# PL_Ethernet.net
KiCad netlist of a schematic drawn in Altium Designer
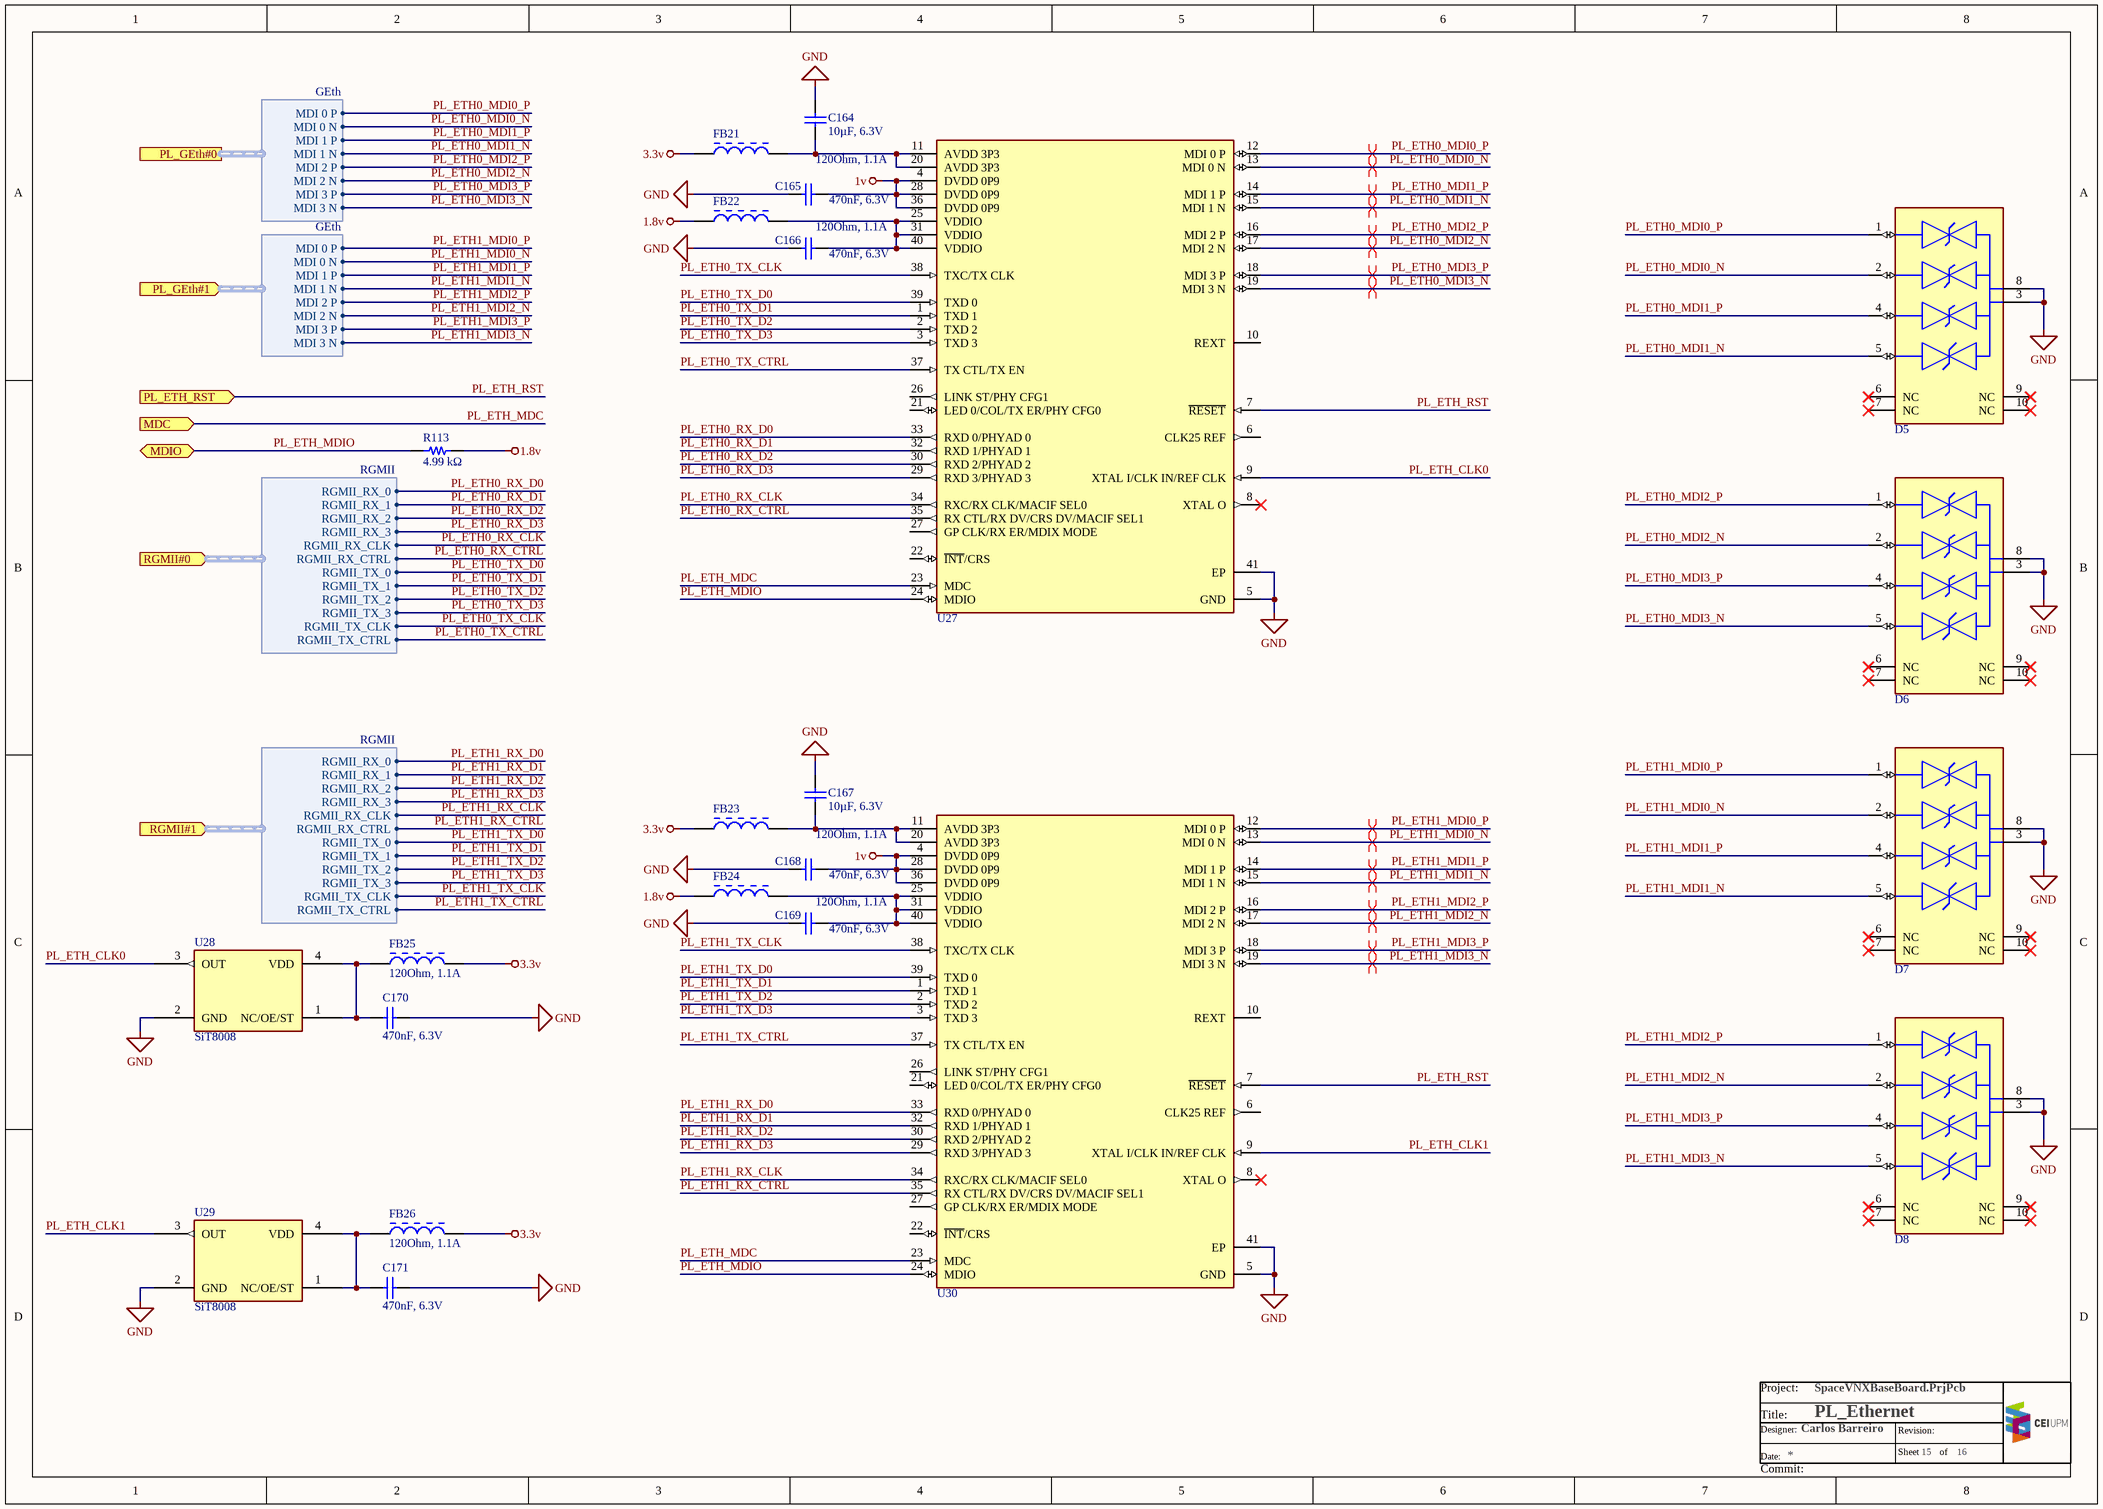
[diagram p0: PL_Ethernet.SchDoc]

(export (version "E")
  (design (tool "Eeschema 10.0.6"))
  (components
    (comp (ref "C164")
      (value "10µF, 6.3V")
      (footprint "WURTH_WCAP-CSGP_0402")
      (description "WCAP-CSGP Multilayer Ceramic Chip Capacitor, General Purpose, size 0402, X5R, 10uF, 6.3V")
      (fields
        (field (name "MANUFACTURER PART NUMBER") "885012105020")
        (field (name "MANUFACTURER") "Wurth Elektronik")
      )
      (libsource (lib "SpaceVNX") (part "885012105020"))
    )
    (comp (ref "C165")
      (value "470nF, 6.3V")
      (footprint "WURTH_WCAP-CSGP_0402")
      (description "WCAP-CSGP Multilayer Ceramic Chip Capacitor, General Purpose, size 0402, X5R, 470nF, 6.3V")
      (fields
        (field (name "MANUFACTURER PART NUMBER") "885012105004")
        (field (name "MANUFACTURER") "Wurth Elektronik")
      )
      (libsource (lib "SpaceVNX") (part "885012105004"))
    )
    (comp (ref "C166")
      (value "470nF, 6.3V")
      (footprint "WURTH_WCAP-CSGP_0402")
      (description "WCAP-CSGP Multilayer Ceramic Chip Capacitor, General Purpose, size 0402, X5R, 470nF, 6.3V")
      (fields
        (field (name "MANUFACTURER PART NUMBER") "885012105004")
        (field (name "MANUFACTURER") "Wurth Elektronik")
      )
      (libsource (lib "SpaceVNX") (part "885012105004"))
    )
    (comp (ref "C167")
      (value "10µF, 6.3V")
      (footprint "WURTH_WCAP-CSGP_0402")
      (description "WCAP-CSGP Multilayer Ceramic Chip Capacitor, General Purpose, size 0402, X5R, 10uF, 6.3V")
      (fields
        (field (name "MANUFACTURER PART NUMBER") "885012105020")
        (field (name "MANUFACTURER") "Wurth Elektronik")
      )
      (libsource (lib "SpaceVNX") (part "885012105020"))
    )
    (comp (ref "C168")
      (value "470nF, 6.3V")
      (footprint "WURTH_WCAP-CSGP_0402")
      (description "WCAP-CSGP Multilayer Ceramic Chip Capacitor, General Purpose, size 0402, X5R, 470nF, 6.3V")
      (fields
        (field (name "MANUFACTURER PART NUMBER") "885012105004")
        (field (name "MANUFACTURER") "Wurth Elektronik")
      )
      (libsource (lib "SpaceVNX") (part "885012105004"))
    )
    (comp (ref "C169")
      (value "470nF, 6.3V")
      (footprint "WURTH_WCAP-CSGP_0402")
      (description "WCAP-CSGP Multilayer Ceramic Chip Capacitor, General Purpose, size 0402, X5R, 470nF, 6.3V")
      (fields
        (field (name "MANUFACTURER PART NUMBER") "885012105004")
        (field (name "MANUFACTURER") "Wurth Elektronik")
      )
      (libsource (lib "SpaceVNX") (part "885012105004"))
    )
    (comp (ref "C170")
      (value "470nF, 6.3V")
      (footprint "WURTH_WCAP-CSGP_0402")
      (description "WCAP-CSGP Multilayer Ceramic Chip Capacitor, General Purpose, size 0402, X5R, 470nF, 6.3V")
      (fields
        (field (name "MANUFACTURER PART NUMBER") "885012105004")
        (field (name "MANUFACTURER") "Wurth Elektronik")
      )
      (libsource (lib "SpaceVNX") (part "885012105004"))
    )
    (comp (ref "C171")
      (value "470nF, 6.3V")
      (footprint "WURTH_WCAP-CSGP_0402")
      (description "WCAP-CSGP Multilayer Ceramic Chip Capacitor, General Purpose, size 0402, X5R, 470nF, 6.3V")
      (fields
        (field (name "MANUFACTURER PART NUMBER") "885012105004")
        (field (name "MANUFACTURER") "Wurth Elektronik")
      )
      (libsource (lib "SpaceVNX") (part "885012105004"))
    )
    (comp (ref "D5")
      (value "ESD204DQAR")
      (footprint "TEXAS_USON10")
      (description "ESD204 4-Channel Low-Capacitance Surge and ESD Protection Diode")
      (libsource (lib "SpaceVNX") (part "ESD204DQAR"))
    )
    (comp (ref "D6")
      (value "ESD204DQAR")
      (footprint "TEXAS_USON10")
      (description "ESD204 4-Channel Low-Capacitance Surge and ESD Protection Diode")
      (libsource (lib "SpaceVNX") (part "ESD204DQAR"))
    )
    (comp (ref "D7")
      (value "ESD204DQAR")
      (footprint "TEXAS_USON10")
      (description "ESD204 4-Channel Low-Capacitance Surge and ESD Protection Diode")
      (libsource (lib "SpaceVNX") (part "ESD204DQAR"))
    )
    (comp (ref "D8")
      (value "ESD204DQAR")
      (footprint "TEXAS_USON10")
      (description "ESD204 4-Channel Low-Capacitance Surge and ESD Protection Diode")
      (libsource (lib "SpaceVNX") (part "ESD204DQAR"))
    )
    (comp (ref "FB21")
      (value "120Ohm, 1.1A")
      (footprint "WURTH-CBF_0402")
      (description "WE-CBF SMT EMI Suppression Ferrite Bead, size 0402, 120Ohm, 1.1A")
      (fields
        (field (name "MANUFACTURER PART NUMBER") "74279271")
        (field (name "MANUFACTURER") "Wurth Elektronik")
      )
      (libsource (lib "SpaceVNX") (part "74279271"))
    )
    (comp (ref "FB22")
      (value "120Ohm, 1.1A")
      (footprint "WURTH-CBF_0402")
      (description "WE-CBF SMT EMI Suppression Ferrite Bead, size 0402, 120Ohm, 1.1A")
      (fields
        (field (name "MANUFACTURER PART NUMBER") "74279271")
        (field (name "MANUFACTURER") "Wurth Elektronik")
      )
      (libsource (lib "SpaceVNX") (part "74279271"))
    )
    (comp (ref "FB23")
      (value "120Ohm, 1.1A")
      (footprint "WURTH-CBF_0402")
      (description "WE-CBF SMT EMI Suppression Ferrite Bead, size 0402, 120Ohm, 1.1A")
      (fields
        (field (name "MANUFACTURER PART NUMBER") "74279271")
        (field (name "MANUFACTURER") "Wurth Elektronik")
      )
      (libsource (lib "SpaceVNX") (part "74279271"))
    )
    (comp (ref "FB24")
      (value "120Ohm, 1.1A")
      (footprint "WURTH-CBF_0402")
      (description "WE-CBF SMT EMI Suppression Ferrite Bead, size 0402, 120Ohm, 1.1A")
      (fields
        (field (name "MANUFACTURER PART NUMBER") "74279271")
        (field (name "MANUFACTURER") "Wurth Elektronik")
      )
      (libsource (lib "SpaceVNX") (part "74279271"))
    )
    (comp (ref "FB25")
      (value "120Ohm, 1.1A")
      (footprint "WURTH-CBF_0402")
      (description "WE-CBF SMT EMI Suppression Ferrite Bead, size 0402, 120Ohm, 1.1A")
      (fields
        (field (name "MANUFACTURER PART NUMBER") "74279271")
        (field (name "MANUFACTURER") "Wurth Elektronik")
      )
      (libsource (lib "SpaceVNX") (part "74279271"))
    )
    (comp (ref "FB26")
      (value "120Ohm, 1.1A")
      (footprint "WURTH-CBF_0402")
      (description "WE-CBF SMT EMI Suppression Ferrite Bead, size 0402, 120Ohm, 1.1A")
      (fields
        (field (name "MANUFACTURER PART NUMBER") "74279271")
        (field (name "MANUFACTURER") "Wurth Elektronik")
      )
      (libsource (lib "SpaceVNX") (part "74279271"))
    )
    (comp (ref "R113")
      (value "4.99 kΩ")
      (footprint "PANASONIC_ERJ2G_0402")
      (description "General Purpose Thick Film Chip Resistors")
      (fields (field (name "MANUFACTURER") "Panasonic"))
      (libsource (lib "SpaceVNX") (part "ERJ2RKF4991X"))
    )
    (comp (ref "U27")
      (value "ADIN1300CCPZ")
      (footprint "ADI_LFCSP40")
      (description "Robust, Industrial, Low Latency and Low Power 10 Mbps, 100 Mbps, and 1 Gbps Ethernet PHY")
      (libsource (lib "SpaceVNX") (part "ADIN1300CCPZ"))
    )
    (comp (ref "U28")
      (value "SiT8008")
      (footprint "SiTime_5032_4")
      (libsource (lib "SpaceVNX") (part "SiT8008"))
    )
    (comp (ref "U29")
      (value "SiT8008")
      (footprint "SiTime_5032_4")
      (libsource (lib "SpaceVNX") (part "SiT8008"))
    )
    (comp (ref "U30")
      (value "ADIN1300CCPZ")
      (footprint "ADI_LFCSP40")
      (description "Robust, Industrial, Low Latency and Low Power 10 Mbps, 100 Mbps, and 1 Gbps Ethernet PHY")
      (libsource (lib "SpaceVNX") (part "ADIN1300CCPZ"))
    )
  )
  (nets
    (net (code "3") (name "/PL_ETH0_MDI0_N") (class "Default")
      (node (ref "D5") (pin "2") (pinfunction "IO2_2") (pintype "bidirectional"))
      (node (ref "U27") (pin "13") (pinfunction "MDI_0_N_13") (pintype "bidirectional"))
    )
    (net (code "4") (name "/PL_ETH0_MDI0_P") (class "Default")
      (node (ref "D5") (pin "1") (pinfunction "IO1_1") (pintype "bidirectional"))
      (node (ref "U27") (pin "12") (pinfunction "MDI_0_P_12") (pintype "bidirectional"))
    )
    (net (code "5") (name "/PL_ETH0_MDI1_N") (class "Default")
      (node (ref "D5") (pin "5") (pinfunction "IO4_5") (pintype "bidirectional"))
      (node (ref "U27") (pin "15") (pinfunction "MDI_1_N_15") (pintype "bidirectional"))
    )
    (net (code "6") (name "/PL_ETH0_MDI1_P") (class "Default")
      (node (ref "D5") (pin "4") (pinfunction "IO3_4") (pintype "bidirectional"))
      (node (ref "U27") (pin "14") (pinfunction "MDI_1_P_14") (pintype "bidirectional"))
    )
    (net (code "7") (name "/PL_ETH0_MDI2_N") (class "Default")
      (node (ref "D6") (pin "2") (pinfunction "IO2_2") (pintype "bidirectional"))
      (node (ref "U27") (pin "17") (pinfunction "MDI_2_N_17") (pintype "bidirectional"))
    )
    (net (code "8") (name "/PL_ETH0_MDI2_P") (class "Default")
      (node (ref "D6") (pin "1") (pinfunction "IO1_1") (pintype "bidirectional"))
      (node (ref "U27") (pin "16") (pinfunction "MDI_2_P_16") (pintype "bidirectional"))
    )
    (net (code "9") (name "/PL_ETH0_MDI3_N") (class "Default")
      (node (ref "D6") (pin "5") (pinfunction "IO4_5") (pintype "bidirectional"))
      (node (ref "U27") (pin "19") (pinfunction "MDI_3_N_19") (pintype "bidirectional"))
    )
    (net (code "10") (name "/PL_ETH0_MDI3_P") (class "Default")
      (node (ref "D6") (pin "4") (pinfunction "IO3_4") (pintype "bidirectional"))
      (node (ref "U27") (pin "18") (pinfunction "MDI_3_P_18") (pintype "bidirectional"))
    )
    (net (code "11") (name "/PL_ETH0_RX_CLK") (class "Default")
      (node (ref "U27") (pin "34") (pinfunction "RXC/RX_CLK/MACIF_SEL0_34") (pintype "output"))
    )
    (net (code "12") (name "/PL_ETH0_RX_CTRL") (class "Default")
      (node (ref "U27") (pin "35") (pinfunction "RX_CTL/RX_DV/CRS_DV/MACIF_SEL1_35") (pintype "output"))
    )
    (net (code "13") (name "/PL_ETH0_RX_D0") (class "Default")
      (node (ref "U27") (pin "33") (pinfunction "RXD_0/PHYAD_0_33") (pintype "output"))
    )
    (net (code "14") (name "/PL_ETH0_RX_D1") (class "Default")
      (node (ref "U27") (pin "32") (pinfunction "RXD_1/PHYAD_1_32") (pintype "output"))
    )
    (net (code "15") (name "/PL_ETH0_RX_D2") (class "Default")
      (node (ref "U27") (pin "30") (pinfunction "RXD_2/PHYAD_2_30") (pintype "output"))
    )
    (net (code "16") (name "/PL_ETH0_RX_D3") (class "Default")
      (node (ref "U27") (pin "29") (pinfunction "RXD_3/PHYAD_3_29") (pintype "output"))
    )
    (net (code "17") (name "/PL_ETH0_TX_CLK") (class "Default")
      (node (ref "U27") (pin "38") (pinfunction "TXC/TX_CLK_38") (pintype "input"))
    )
    (net (code "18") (name "/PL_ETH0_TX_CTRL") (class "Default")
      (node (ref "U27") (pin "37") (pinfunction "TX_CTL/TX_EN_37") (pintype "input"))
    )
    (net (code "19") (name "/PL_ETH0_TX_D0") (class "Default")
      (node (ref "U27") (pin "39") (pinfunction "TXD_0_39") (pintype "input"))
    )
    (net (code "20") (name "/PL_ETH0_TX_D1") (class "Default")
      (node (ref "U27") (pin "1") (pinfunction "TXD_1_1") (pintype "input"))
    )
    (net (code "21") (name "/PL_ETH0_TX_D2") (class "Default")
      (node (ref "U27") (pin "2") (pinfunction "TXD_2_2") (pintype "input"))
    )
    (net (code "22") (name "/PL_ETH0_TX_D3") (class "Default")
      (node (ref "U27") (pin "3") (pinfunction "TXD_3_3") (pintype "input"))
    )
    (net (code "23") (name "/PL_ETH1_MDI0_N") (class "Default")
      (node (ref "D7") (pin "2") (pinfunction "IO2_2") (pintype "bidirectional"))
      (node (ref "U30") (pin "13") (pinfunction "MDI_0_N_13") (pintype "bidirectional"))
    )
    (net (code "24") (name "/PL_ETH1_MDI0_P") (class "Default")
      (node (ref "D7") (pin "1") (pinfunction "IO1_1") (pintype "bidirectional"))
      (node (ref "U30") (pin "12") (pinfunction "MDI_0_P_12") (pintype "bidirectional"))
    )
    (net (code "25") (name "/PL_ETH1_MDI1_N") (class "Default")
      (node (ref "D7") (pin "5") (pinfunction "IO4_5") (pintype "bidirectional"))
      (node (ref "U30") (pin "15") (pinfunction "MDI_1_N_15") (pintype "bidirectional"))
    )
    (net (code "26") (name "/PL_ETH1_MDI1_P") (class "Default")
      (node (ref "D7") (pin "4") (pinfunction "IO3_4") (pintype "bidirectional"))
      (node (ref "U30") (pin "14") (pinfunction "MDI_1_P_14") (pintype "bidirectional"))
    )
    (net (code "27") (name "/PL_ETH1_MDI2_N") (class "Default")
      (node (ref "D8") (pin "2") (pinfunction "IO2_2") (pintype "bidirectional"))
      (node (ref "U30") (pin "17") (pinfunction "MDI_2_N_17") (pintype "bidirectional"))
    )
    (net (code "28") (name "/PL_ETH1_MDI2_P") (class "Default")
      (node (ref "D8") (pin "1") (pinfunction "IO1_1") (pintype "bidirectional"))
      (node (ref "U30") (pin "16") (pinfunction "MDI_2_P_16") (pintype "bidirectional"))
    )
    (net (code "29") (name "/PL_ETH1_MDI3_N") (class "Default")
      (node (ref "D8") (pin "5") (pinfunction "IO4_5") (pintype "bidirectional"))
      (node (ref "U30") (pin "19") (pinfunction "MDI_3_N_19") (pintype "bidirectional"))
    )
    (net (code "30") (name "/PL_ETH1_MDI3_P") (class "Default")
      (node (ref "D8") (pin "4") (pinfunction "IO3_4") (pintype "bidirectional"))
      (node (ref "U30") (pin "18") (pinfunction "MDI_3_P_18") (pintype "bidirectional"))
    )
    (net (code "31") (name "/PL_ETH1_RX_CLK") (class "Default")
      (node (ref "U30") (pin "34") (pinfunction "RXC/RX_CLK/MACIF_SEL0_34") (pintype "output"))
    )
    (net (code "32") (name "/PL_ETH1_RX_CTRL") (class "Default")
      (node (ref "U30") (pin "35") (pinfunction "RX_CTL/RX_DV/CRS_DV/MACIF_SEL1_35") (pintype "output"))
    )
    (net (code "33") (name "/PL_ETH1_RX_D0") (class "Default")
      (node (ref "U30") (pin "33") (pinfunction "RXD_0/PHYAD_0_33") (pintype "output"))
    )
    (net (code "34") (name "/PL_ETH1_RX_D1") (class "Default")
      (node (ref "U30") (pin "32") (pinfunction "RXD_1/PHYAD_1_32") (pintype "output"))
    )
    (net (code "35") (name "/PL_ETH1_RX_D2") (class "Default")
      (node (ref "U30") (pin "30") (pinfunction "RXD_2/PHYAD_2_30") (pintype "output"))
    )
    (net (code "36") (name "/PL_ETH1_RX_D3") (class "Default")
      (node (ref "U30") (pin "29") (pinfunction "RXD_3/PHYAD_3_29") (pintype "output"))
    )
    (net (code "37") (name "/PL_ETH1_TX_CLK") (class "Default")
      (node (ref "U30") (pin "38") (pinfunction "TXC/TX_CLK_38") (pintype "input"))
    )
    (net (code "38") (name "/PL_ETH1_TX_CTRL") (class "Default")
      (node (ref "U30") (pin "37") (pinfunction "TX_CTL/TX_EN_37") (pintype "input"))
    )
    (net (code "39") (name "/PL_ETH1_TX_D0") (class "Default")
      (node (ref "U30") (pin "39") (pinfunction "TXD_0_39") (pintype "input"))
    )
    (net (code "40") (name "/PL_ETH1_TX_D1") (class "Default")
      (node (ref "U30") (pin "1") (pinfunction "TXD_1_1") (pintype "input"))
    )
    (net (code "41") (name "/PL_ETH1_TX_D2") (class "Default")
      (node (ref "U30") (pin "2") (pinfunction "TXD_2_2") (pintype "input"))
    )
    (net (code "42") (name "/PL_ETH1_TX_D3") (class "Default")
      (node (ref "U30") (pin "3") (pinfunction "TXD_3_3") (pintype "input"))
    )
    (net (code "43") (name "/PL_ETH_CLK0") (class "Default")
      (node (ref "U27") (pin "9") (pinfunction "XTAL_I/CLK_IN/REF_CLK_9") (pintype "input"))
      (node (ref "U28") (pin "3") (pinfunction "OUT_3") (pintype "output"))
    )
    (net (code "44") (name "/PL_ETH_CLK1") (class "Default")
      (node (ref "U29") (pin "3") (pinfunction "OUT_3") (pintype "output"))
      (node (ref "U30") (pin "9") (pinfunction "XTAL_I/CLK_IN/REF_CLK_9") (pintype "input"))
    )
    (net (code "45") (name "/PL_ETH_MDC") (class "Default")
      (node (ref "U27") (pin "23") (pinfunction "MDC_23") (pintype "input"))
      (node (ref "U30") (pin "23") (pinfunction "MDC_23") (pintype "input"))
    )
    (net (code "46") (name "/PL_ETH_MDIO") (class "Default")
      (node (ref "R113") (pin "1") (pinfunction "1_1") (pintype "passive"))
      (node (ref "U27") (pin "24") (pinfunction "MDIO_24") (pintype "bidirectional"))
      (node (ref "U30") (pin "24") (pinfunction "MDIO_24") (pintype "bidirectional"))
    )
    (net (code "47") (name "/PL_ETH_RST") (class "Default")
      (node (ref "U27") (pin "7") (pinfunction "~{RESET}_7") (pintype "input"))
      (node (ref "U30") (pin "7") (pinfunction "~{RESET}_7") (pintype "input"))
    )
    (net (code "50") (name "1.8v") (class "Default")
      (node (ref "FB22") (pin "1") (pinfunction "1_1") (pintype "passive"))
      (node (ref "FB24") (pin "1") (pinfunction "1_1") (pintype "passive"))
      (node (ref "R113") (pin "2") (pinfunction "2_2") (pintype "passive"))
    )
    (net (code "51") (name "1v") (class "Default")
      (node (ref "C165") (pin "2") (pinfunction "2_2") (pintype "passive"))
      (node (ref "C168") (pin "2") (pinfunction "2_2") (pintype "passive"))
      (node (ref "U27") (pin "28") (pinfunction "DVDD_0P9_28") (pintype "power_in"))
      (node (ref "U27") (pin "36") (pinfunction "DVDD_0P9_36") (pintype "power_in"))
      (node (ref "U27") (pin "4") (pinfunction "DVDD_0P9_4") (pintype "power_in"))
      (node (ref "U30") (pin "28") (pinfunction "DVDD_0P9_28") (pintype "power_in"))
      (node (ref "U30") (pin "36") (pinfunction "DVDD_0P9_36") (pintype "power_in"))
      (node (ref "U30") (pin "4") (pinfunction "DVDD_0P9_4") (pintype "power_in"))
    )
    (net (code "52") (name "3.3v") (class "Default")
      (node (ref "FB21") (pin "1") (pinfunction "1_1") (pintype "passive"))
      (node (ref "FB23") (pin "1") (pinfunction "1_1") (pintype "passive"))
      (node (ref "FB25") (pin "2") (pinfunction "2_2") (pintype "passive"))
      (node (ref "FB26") (pin "2") (pinfunction "2_2") (pintype "passive"))
    )
    (net (code "53") (name "GND") (class "Default")
      (node (ref "C164") (pin "2") (pinfunction "2_2") (pintype "passive"))
      (node (ref "C165") (pin "1") (pinfunction "1_1") (pintype "passive"))
      (node (ref "C166") (pin "1") (pinfunction "1_1") (pintype "passive"))
      (node (ref "C167") (pin "2") (pinfunction "2_2") (pintype "passive"))
      (node (ref "C168") (pin "1") (pinfunction "1_1") (pintype "passive"))
      (node (ref "C169") (pin "1") (pinfunction "1_1") (pintype "passive"))
      (node (ref "C170") (pin "1") (pinfunction "1_1") (pintype "passive"))
      (node (ref "C171") (pin "1") (pinfunction "1_1") (pintype "passive"))
      (node (ref "D5") (pin "3") (pinfunction "GND_3") (pintype "power_in"))
      (node (ref "D5") (pin "8") (pinfunction "GND_8") (pintype "power_in"))
      (node (ref "D6") (pin "3") (pinfunction "GND_3") (pintype "power_in"))
      (node (ref "D6") (pin "8") (pinfunction "GND_8") (pintype "power_in"))
      (node (ref "D7") (pin "3") (pinfunction "GND_3") (pintype "power_in"))
      (node (ref "D7") (pin "8") (pinfunction "GND_8") (pintype "power_in"))
      (node (ref "D8") (pin "3") (pinfunction "GND_3") (pintype "power_in"))
      (node (ref "D8") (pin "8") (pinfunction "GND_8") (pintype "power_in"))
      (node (ref "U27") (pin "41") (pinfunction "EP_41") (pintype "power_in"))
      (node (ref "U27") (pin "5") (pinfunction "GND_5") (pintype "power_in"))
      (node (ref "U28") (pin "2") (pinfunction "GND_2") (pintype "passive"))
      (node (ref "U29") (pin "2") (pinfunction "GND_2") (pintype "passive"))
      (node (ref "U30") (pin "41") (pinfunction "EP_41") (pintype "power_in"))
      (node (ref "U30") (pin "5") (pinfunction "GND_5") (pintype "power_in"))
    )
    (net (code "54") (name "Net-(C164-Pad1)") (class "Default")
      (node (ref "C164") (pin "1") (pinfunction "1_1") (pintype "passive"))
      (node (ref "FB21") (pin "2") (pinfunction "2_2") (pintype "passive"))
      (node (ref "U27") (pin "11") (pinfunction "AVDD_3P3_11") (pintype "power_in"))
      (node (ref "U27") (pin "20") (pinfunction "AVDD_3P3_20") (pintype "power_in"))
    )
    (net (code "55") (name "Net-(C166-Pad2)") (class "Default")
      (node (ref "C166") (pin "2") (pinfunction "2_2") (pintype "passive"))
      (node (ref "FB22") (pin "2") (pinfunction "2_2") (pintype "passive"))
      (node (ref "U27") (pin "25") (pinfunction "VDDIO_25") (pintype "power_in"))
      (node (ref "U27") (pin "31") (pinfunction "VDDIO_31") (pintype "power_in"))
      (node (ref "U27") (pin "40") (pinfunction "VDDIO_40") (pintype "power_in"))
    )
    (net (code "56") (name "Net-(C167-Pad1)") (class "Default")
      (node (ref "C167") (pin "1") (pinfunction "1_1") (pintype "passive"))
      (node (ref "FB23") (pin "2") (pinfunction "2_2") (pintype "passive"))
      (node (ref "U30") (pin "11") (pinfunction "AVDD_3P3_11") (pintype "power_in"))
      (node (ref "U30") (pin "20") (pinfunction "AVDD_3P3_20") (pintype "power_in"))
    )
    (net (code "57") (name "Net-(C169-Pad2)") (class "Default")
      (node (ref "C169") (pin "2") (pinfunction "2_2") (pintype "passive"))
      (node (ref "FB24") (pin "2") (pinfunction "2_2") (pintype "passive"))
      (node (ref "U30") (pin "25") (pinfunction "VDDIO_25") (pintype "power_in"))
      (node (ref "U30") (pin "31") (pinfunction "VDDIO_31") (pintype "power_in"))
      (node (ref "U30") (pin "40") (pinfunction "VDDIO_40") (pintype "power_in"))
    )
    (net (code "58") (name "Net-(U28-NC{slash}OE{slash}ST)") (class "Default")
      (node (ref "C170") (pin "2") (pinfunction "2_2") (pintype "passive"))
      (node (ref "FB25") (pin "1") (pinfunction "1_1") (pintype "passive"))
      (node (ref "U28") (pin "1") (pinfunction "NC/OE/ST_1") (pintype "passive"))
      (node (ref "U28") (pin "4") (pinfunction "VDD_4") (pintype "passive"))
    )
    (net (code "59") (name "Net-(U29-NC{slash}OE{slash}ST)") (class "Default")
      (node (ref "C171") (pin "2") (pinfunction "2_2") (pintype "passive"))
      (node (ref "FB26") (pin "1") (pinfunction "1_1") (pintype "passive"))
      (node (ref "U29") (pin "1") (pinfunction "NC/OE/ST_1") (pintype "passive"))
      (node (ref "U29") (pin "4") (pinfunction "VDD_4") (pintype "passive"))
    )
    (net (code "60") (name "unconnected-(D5-NC-Pad6)") (class "Default")
      (node (ref "D5") (pin "6") (pinfunction "NC_6") (pintype "passive+no_connect"))
    )
    (net (code "61") (name "unconnected-(D5-NC-Pad7)") (class "Default")
      (node (ref "D5") (pin "7") (pinfunction "NC_7") (pintype "passive+no_connect"))
    )
    (net (code "62") (name "unconnected-(D5-NC-Pad9)") (class "Default")
      (node (ref "D5") (pin "9") (pinfunction "NC_9") (pintype "passive+no_connect"))
    )
    (net (code "63") (name "unconnected-(D5-NC-Pad10)") (class "Default")
      (node (ref "D5") (pin "10") (pinfunction "NC_10") (pintype "passive+no_connect"))
    )
    (net (code "64") (name "unconnected-(D6-NC-Pad6)") (class "Default")
      (node (ref "D6") (pin "6") (pinfunction "NC_6") (pintype "passive+no_connect"))
    )
    (net (code "65") (name "unconnected-(D6-NC-Pad7)") (class "Default")
      (node (ref "D6") (pin "7") (pinfunction "NC_7") (pintype "passive+no_connect"))
    )
    (net (code "66") (name "unconnected-(D6-NC-Pad9)") (class "Default")
      (node (ref "D6") (pin "9") (pinfunction "NC_9") (pintype "passive+no_connect"))
    )
    (net (code "67") (name "unconnected-(D6-NC-Pad10)") (class "Default")
      (node (ref "D6") (pin "10") (pinfunction "NC_10") (pintype "passive+no_connect"))
    )
    (net (code "68") (name "unconnected-(D7-NC-Pad6)") (class "Default")
      (node (ref "D7") (pin "6") (pinfunction "NC_6") (pintype "passive+no_connect"))
    )
    (net (code "69") (name "unconnected-(D7-NC-Pad7)") (class "Default")
      (node (ref "D7") (pin "7") (pinfunction "NC_7") (pintype "passive+no_connect"))
    )
    (net (code "70") (name "unconnected-(D7-NC-Pad9)") (class "Default")
      (node (ref "D7") (pin "9") (pinfunction "NC_9") (pintype "passive+no_connect"))
    )
    (net (code "71") (name "unconnected-(D7-NC-Pad10)") (class "Default")
      (node (ref "D7") (pin "10") (pinfunction "NC_10") (pintype "passive+no_connect"))
    )
    (net (code "72") (name "unconnected-(D8-NC-Pad6)") (class "Default")
      (node (ref "D8") (pin "6") (pinfunction "NC_6") (pintype "passive+no_connect"))
    )
    (net (code "73") (name "unconnected-(D8-NC-Pad7)") (class "Default")
      (node (ref "D8") (pin "7") (pinfunction "NC_7") (pintype "passive+no_connect"))
    )
    (net (code "74") (name "unconnected-(D8-NC-Pad9)") (class "Default")
      (node (ref "D8") (pin "9") (pinfunction "NC_9") (pintype "passive+no_connect"))
    )
    (net (code "75") (name "unconnected-(D8-NC-Pad10)") (class "Default")
      (node (ref "D8") (pin "10") (pinfunction "NC_10") (pintype "passive+no_connect"))
    )
    (net (code "76") (name "unconnected-(U27-CLK25_REF-Pad6)") (class "Default")
      (node (ref "U27") (pin "6") (pinfunction "CLK25_REF_6") (pintype "output"))
    )
    (net (code "77") (name "unconnected-(U27-GP_CLK{slash}RX_ER{slash}MDIX_MODE-Pad27)") (class "Default")
      (node (ref "U27") (pin "27") (pinfunction "GP_CLK/RX_ER/MDIX_MODE_27") (pintype "output"))
    )
    (net (code "78") (name "unconnected-(U27-LED_0{slash}COL{slash}TX_ER{slash}PHY_CFG0-Pad21)") (class "Default")
      (node (ref "U27") (pin "21") (pinfunction "LED_0/COL/TX_ER/PHY_CFG0_21") (pintype "bidirectional"))
    )
    (net (code "79") (name "unconnected-(U27-LINK_ST{slash}PHY_CFG1-Pad26)") (class "Default")
      (node (ref "U27") (pin "26") (pinfunction "LINK_ST/PHY_CFG1_26") (pintype "output"))
    )
    (net (code "80") (name "unconnected-(U27-REXT-Pad10)") (class "Default")
      (node (ref "U27") (pin "10") (pinfunction "REXT_10") (pintype "passive"))
    )
    (net (code "81") (name "unconnected-(U27-XTAL_O-Pad8)") (class "Default")
      (node (ref "U27") (pin "8") (pinfunction "XTAL_O_8") (pintype "output+no_connect"))
    )
    (net (code "82") (name "unconnected-(U27-~{INT}{slash}CRS-Pad22)") (class "Default")
      (node (ref "U27") (pin "22") (pinfunction "~{INT}/CRS_22") (pintype "bidirectional"))
    )
    (net (code "83") (name "unconnected-(U30-CLK25_REF-Pad6)") (class "Default")
      (node (ref "U30") (pin "6") (pinfunction "CLK25_REF_6") (pintype "output"))
    )
    (net (code "84") (name "unconnected-(U30-GP_CLK{slash}RX_ER{slash}MDIX_MODE-Pad27)") (class "Default")
      (node (ref "U30") (pin "27") (pinfunction "GP_CLK/RX_ER/MDIX_MODE_27") (pintype "output"))
    )
    (net (code "85") (name "unconnected-(U30-LED_0{slash}COL{slash}TX_ER{slash}PHY_CFG0-Pad21)") (class "Default")
      (node (ref "U30") (pin "21") (pinfunction "LED_0/COL/TX_ER/PHY_CFG0_21") (pintype "bidirectional"))
    )
    (net (code "86") (name "unconnected-(U30-LINK_ST{slash}PHY_CFG1-Pad26)") (class "Default")
      (node (ref "U30") (pin "26") (pinfunction "LINK_ST/PHY_CFG1_26") (pintype "output"))
    )
    (net (code "87") (name "unconnected-(U30-REXT-Pad10)") (class "Default")
      (node (ref "U30") (pin "10") (pinfunction "REXT_10") (pintype "passive"))
    )
    (net (code "88") (name "unconnected-(U30-XTAL_O-Pad8)") (class "Default")
      (node (ref "U30") (pin "8") (pinfunction "XTAL_O_8") (pintype "output+no_connect"))
    )
    (net (code "89") (name "unconnected-(U30-~{INT}{slash}CRS-Pad22)") (class "Default")
      (node (ref "U30") (pin "22") (pinfunction "~{INT}/CRS_22") (pintype "bidirectional"))
    )
  )
)
